# Quad_FC_power_V10_6.net
KiCad netlist of a schematic drawn in Altium Designer
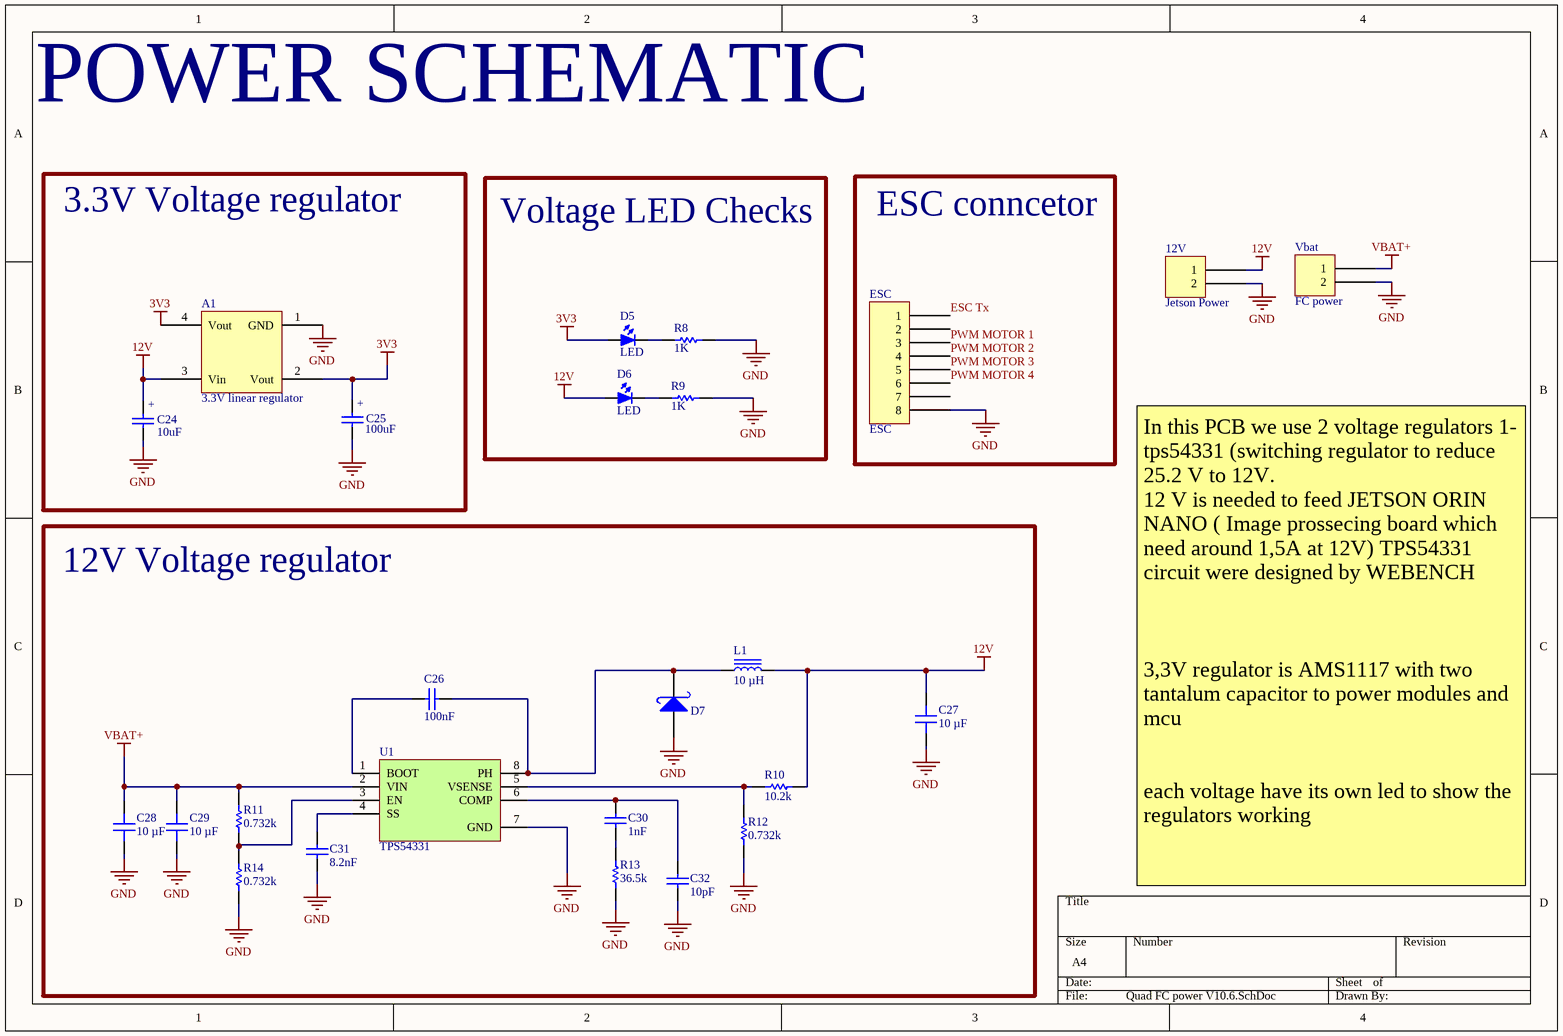
[diagram p0: Quad FC power V10.6.SchDoc]

(export (version "E")
  (design (tool "Eeschema 10.0.6"))
  (components
    (comp (ref "12V")
      (value "Jetson Power")
      (footprint "JST XH B2B-XH-A")
      (description "CONN HEADER VERT 2POS 2.5MM")
      (fields
        (field (name "PART NUMBER") "B2B-XH-A(LF)(SN)")
        (field (name "MANUFACTURER") "JST Sales America Inc.")
      )
      (libsource (lib "Celestial Altium Library - altium_library (1)") (part "2 Pin"))
    )
    (comp (ref "A1")
      (value "3.3V linear regulator")
      (footprint "SOT230P700X180-4N")
      (libsource (lib "Integrated_Library1") (part "ams1117"))
    )
    (comp (ref "C24")
      (value "10uF")
      (footprint "MY_CAP_SMD-B")
      (description "3.5X2.8MM")
      (libsource (lib "AMINLIB") (part "CAP_TANTAL_B"))
    )
    (comp (ref "C25")
      (value "100uF")
      (footprint "MY_CAP_SMD-B")
      (description "3.5X2.8MM")
      (libsource (lib "AMINLIB") (part "CAP_TANTAL_B"))
    )
    (comp (ref "C26")
      (value "100nF")
      (footprint "CAP0603")
      (description "F407VET6 Power CAP")
      (fields (field (name "DESIGNER") "Abbas Basereh"))
      (libsource (lib "2017AbbasBasereh9365731239 -ver1") (part "CAP SMD PACKAGE"))
    )
    (comp (ref "C27")
      (value "10 µF")
      (footprint "CAP 0805_2012")
      (description "CAP CER 10UF 50V X5R 0805")
      (fields
        (field (name "PART NUMBER") "GRM21BR61H106KE43K")
        (field (name "MANUFACTURER") "Murata Electronics")
      )
      (libsource (lib "Celestial Altium Library - altium_library (1)") (part "Capacitor"))
    )
    (comp (ref "C28")
      (value "10 µF")
      (footprint "CAP 0805_2012")
      (description "CAP CER 10UF 50V X5R 0805")
      (fields
        (field (name "PART NUMBER") "GRM21BR61H106KE43K")
        (field (name "MANUFACTURER") "Murata Electronics")
      )
      (libsource (lib "Celestial Altium Library - altium_library (1)") (part "Capacitor"))
    )
    (comp (ref "C29")
      (value "10 µF")
      (footprint "CAP 0805_2012")
      (description "CAP CER 10UF 50V X5R 0805")
      (fields
        (field (name "PART NUMBER") "GRM21BR61H106KE43K")
        (field (name "MANUFACTURER") "Murata Electronics")
      )
      (libsource (lib "Celestial Altium Library - altium_library (1)") (part "Capacitor"))
    )
    (comp (ref "C30")
      (value "1nF")
      (footprint "CAP0603")
      (description "F407VET6 Power CAP")
      (fields (field (name "DESIGNER") "Abbas Basereh"))
      (libsource (lib "2017AbbasBasereh9365731239 -ver1") (part "CAP SMD PACKAGE"))
    )
    (comp (ref "C31")
      (value "8.2nF")
      (footprint "CAP0603")
      (description "F407VET6 Power CAP")
      (fields (field (name "DESIGNER") "Abbas Basereh"))
      (libsource (lib "2017AbbasBasereh9365731239 -ver1") (part "CAP SMD PACKAGE"))
    )
    (comp (ref "C32")
      (value "10pF")
      (footprint "CAP0603")
      (description "F407VET6 Power CAP")
      (fields (field (name "DESIGNER") "Abbas Basereh"))
      (libsource (lib "2017AbbasBasereh9365731239 -ver1") (part "CAP SMD PACKAGE"))
    )
    (comp (ref "D5")
      (value "LED")
      (footprint "0603 - LED")
      (description "Led")
      (fields (field (name "PUBLISHER") "Altium Limited"))
      (libsource (lib "Sajad_Altium_Library") (part "LED"))
    )
    (comp (ref "D6")
      (value "LED")
      (footprint "0603 - LED")
      (description "Led")
      (fields (field (name "PUBLISHER") "Altium Limited"))
      (libsource (lib "Sajad_Altium_Library") (part "LED"))
    )
    (comp (ref "D7")
      (value "1n5822")
      (footprint "SS34:DIOM4226X244N")
      (description "Schottky Rectifiers")
      (fields
        (field (name "MANUFACTURER") "ON Semiconductor/Fairchild")
        (field (name "DESIGNER") "Abbas Basereh")
      )
      (libsource (lib "2017AbbasBasereh9365731239 -ver1") (part "1n5822 SMD"))
    )
    (comp (ref "ESC")
      (value "ESC")
      (footprint "JST BM08B-SRSS-TB")
      (description "CONN HEADER SMD 8POS 1MM")
      (fields (field (name "PART NUMBER") "BM08B-SRSS-TBT(LF)(SN)"))
      (libsource (lib "Celestial Altium Library - altium_library (1)") (part "8 Pin"))
    )
    (comp (ref "L1")
      (value "10 µH")
      (footprint "TAIYO YUDEN NRS8030")
      (description "FIXED IND 10UH 3A 42.9 MOHM SMD")
      (fields (field (name "PART NUMBER") "NRS8030T100MJGJV") (field (name "MANUFACTURER") "Taiyo Yuden"))
      (libsource (lib "Celestial Altium Library - altium_library (1)") (part "Inductor"))
    )
    (comp (ref "R8")
      (value "1K")
      (footprint "RES0603")
      (description "TOTAL SMD RESISTOR PACK")
      (fields (field (name "DESIGNER") "Abbas Basereh"))
      (libsource (lib "2017AbbasBasereh9365731239 -ver1") (part "RES SMD PACKAGE"))
    )
    (comp (ref "R9")
      (value "1K")
      (footprint "RES0603")
      (description "TOTAL SMD RESISTOR PACK")
      (fields (field (name "DESIGNER") "Abbas Basereh"))
      (libsource (lib "2017AbbasBasereh9365731239 -ver1") (part "RES SMD PACKAGE"))
    )
    (comp (ref "R10")
      (value "10.2k")
      (footprint "RES0603")
      (description "TOTAL SMD RESISTOR PACK")
      (fields (field (name "DESIGNER") "Abbas Basereh"))
      (libsource (lib "2017AbbasBasereh9365731239 -ver1") (part "RES SMD PACKAGE"))
    )
    (comp (ref "R11")
      (value "0.732k")
      (footprint "RES0603")
      (description "TOTAL SMD RESISTOR PACK")
      (fields (field (name "DESIGNER") "Abbas Basereh"))
      (libsource (lib "2017AbbasBasereh9365731239 -ver1") (part "RES SMD PACKAGE"))
    )
    (comp (ref "R12")
      (value "0.732k")
      (footprint "RES0603")
      (description "TOTAL SMD RESISTOR PACK")
      (fields (field (name "DESIGNER") "Abbas Basereh"))
      (libsource (lib "2017AbbasBasereh9365731239 -ver1") (part "RES SMD PACKAGE"))
    )
    (comp (ref "R13")
      (value "36.5k")
      (footprint "RES0603")
      (description "TOTAL SMD RESISTOR PACK")
      (fields (field (name "Comment") "36.5K") (field (name "DESIGNER") "Abbas Basereh"))
      (libsource (lib "2017AbbasBasereh9365731239 -ver1") (part "RES SMD PACKAGE"))
    )
    (comp (ref "R14")
      (value "0.732k")
      (footprint "RES0603")
      (description "TOTAL SMD RESISTOR PACK")
      (fields (field (name "DESIGNER") "Abbas Basereh"))
      (libsource (lib "2017AbbasBasereh9365731239 -ver1") (part "RES SMD PACKAGE"))
    )
    (comp (ref "U1")
      (value "TPS54331")
      (footprint "SO8")
      (description "DC/DC Switching Regulators 2A,28V,1MHz Step Down SWIFT DC/D;Output Voltage:0.8 V to 25 V")
      (libsource (lib "Sajad_Altium_Library") (part "TPS54331"))
    )
    (comp (ref "Vbat")
      (value "FC power")
      (footprint "JST XH B2B-XH-A")
      (description "CONN HEADER VERT 2POS 2.5MM")
      (fields
        (field (name "PART NUMBER") "B2B-XH-A(LF)(SN)")
        (field (name "MANUFACTURER") "JST Sales America Inc.")
      )
      (libsource (lib "Celestial Altium Library - altium_library (1)") (part "2 Pin"))
    )
  )
  (nets
    (net (code "1") (name "/ESC Tx") (class "Default")
      (node (ref "ESC") (pin "1") (pinfunction "1_1") (pintype "passive"))
    )
    (net (code "2") (name "/PWM MOTOR 1") (class "Default")
      (node (ref "ESC") (pin "3") (pinfunction "3_3") (pintype "passive"))
    )
    (net (code "3") (name "/PWM MOTOR 2") (class "Default")
      (node (ref "ESC") (pin "4") (pinfunction "4_4") (pintype "passive"))
    )
    (net (code "4") (name "/PWM MOTOR 3") (class "Default")
      (node (ref "ESC") (pin "5") (pinfunction "5_5") (pintype "passive"))
    )
    (net (code "5") (name "/PWM MOTOR 4") (class "Default")
      (node (ref "ESC") (pin "6") (pinfunction "6_6") (pintype "passive"))
    )
    (net (code "6") (name "3V3") (class "Default")
      (node (ref "A1") (pin "2") (pinfunction "Vout_2") (pintype "passive"))
      (node (ref "A1") (pin "4") (pinfunction "Vout_4") (pintype "passive"))
      (node (ref "C25") (pin "+") (pinfunction "+_+") (pintype "passive"))
      (node (ref "D5") (pin "1") (pinfunction "A_1") (pintype "passive"))
    )
    (net (code "7") (name "12V") (class "Default")
      (node (ref "12V") (pin "1") (pinfunction "1_1") (pintype "passive"))
      (node (ref "A1") (pin "3") (pinfunction "Vin_3") (pintype "passive"))
      (node (ref "C24") (pin "+") (pinfunction "+_+") (pintype "passive"))
      (node (ref "C27") (pin "2") (pinfunction "2_2") (pintype "passive"))
      (node (ref "D6") (pin "1") (pinfunction "A_1") (pintype "passive"))
      (node (ref "L1") (pin "2") (pinfunction "2_2") (pintype "passive"))
      (node (ref "R10") (pin "2") (pinfunction "2_2") (pintype "passive"))
    )
    (net (code "8") (name "GND") (class "Default")
      (node (ref "12V") (pin "2") (pinfunction "2_2") (pintype "passive"))
      (node (ref "A1") (pin "1") (pinfunction "GND_1") (pintype "passive"))
      (node (ref "C24") (pin "-") (pinfunction "-_-") (pintype "passive"))
      (node (ref "C25") (pin "-") (pinfunction "-_-") (pintype "passive"))
      (node (ref "C27") (pin "1") (pinfunction "1_1") (pintype "passive"))
      (node (ref "C28") (pin "1") (pinfunction "1_1") (pintype "passive"))
      (node (ref "C29") (pin "1") (pinfunction "1_1") (pintype "passive"))
      (node (ref "C31") (pin "2") (pinfunction "2_2") (pintype "passive"))
      (node (ref "C32") (pin "2") (pinfunction "2_2") (pintype "passive"))
      (node (ref "D7") (pin "1") (pinfunction "A_1") (pintype "passive"))
      (node (ref "ESC") (pin "8") (pinfunction "8_8") (pintype "passive"))
      (node (ref "R12") (pin "1") (pinfunction "1_1") (pintype "passive"))
      (node (ref "R13") (pin "1") (pinfunction "1_1") (pintype "passive"))
      (node (ref "R14") (pin "1") (pinfunction "1_1") (pintype "passive"))
      (node (ref "R8") (pin "2") (pinfunction "2_2") (pintype "passive"))
      (node (ref "R9") (pin "2") (pinfunction "2_2") (pintype "passive"))
      (node (ref "U1") (pin "7") (pinfunction "GND_7") (pintype "passive"))
      (node (ref "Vbat") (pin "2") (pinfunction "2_2") (pintype "passive"))
    )
    (net (code "9") (name "Net-(C30-Pad2)") (class "Default")
      (node (ref "C30") (pin "2") (pinfunction "2_2") (pintype "passive"))
      (node (ref "R13") (pin "2") (pinfunction "2_2") (pintype "passive"))
    )
    (net (code "10") (name "Net-(D5-K)") (class "Default")
      (node (ref "D5") (pin "2") (pinfunction "K_2") (pintype "passive"))
      (node (ref "R8") (pin "1") (pinfunction "1_1") (pintype "passive"))
    )
    (net (code "11") (name "Net-(D6-K)") (class "Default")
      (node (ref "D6") (pin "2") (pinfunction "K_2") (pintype "passive"))
      (node (ref "R9") (pin "1") (pinfunction "1_1") (pintype "passive"))
    )
    (net (code "12") (name "Net-(D7-K)") (class "Default")
      (node (ref "C26") (pin "1") (pinfunction "1_1") (pintype "passive"))
      (node (ref "D7") (pin "2") (pinfunction "K_2") (pintype "passive"))
      (node (ref "L1") (pin "1") (pinfunction "1_1") (pintype "passive"))
      (node (ref "U1") (pin "8") (pinfunction "PH_8") (pintype "open_collector"))
    )
    (net (code "13") (name "Net-(U1-BOOT)") (class "Default")
      (node (ref "C26") (pin "2") (pinfunction "2_2") (pintype "passive"))
      (node (ref "U1") (pin "1") (pinfunction "BOOT_1") (pintype "passive"))
    )
    (net (code "14") (name "Net-(U1-COMP)") (class "Default")
      (node (ref "C30") (pin "1") (pinfunction "1_1") (pintype "passive"))
      (node (ref "C32") (pin "1") (pinfunction "1_1") (pintype "passive"))
      (node (ref "U1") (pin "6") (pinfunction "COMP_6") (pintype "power_in"))
    )
    (net (code "15") (name "Net-(U1-EN)") (class "Default")
      (node (ref "R11") (pin "1") (pinfunction "1_1") (pintype "passive"))
      (node (ref "R14") (pin "2") (pinfunction "2_2") (pintype "passive"))
      (node (ref "U1") (pin "3") (pinfunction "EN_3") (pintype "passive"))
    )
    (net (code "16") (name "Net-(U1-SS)") (class "Default")
      (node (ref "C31") (pin "1") (pinfunction "1_1") (pintype "passive"))
      (node (ref "U1") (pin "4") (pinfunction "SS_4") (pintype "power_in"))
    )
    (net (code "17") (name "Net-(U1-VSENSE)") (class "Default")
      (node (ref "R10") (pin "1") (pinfunction "1_1") (pintype "passive"))
      (node (ref "R12") (pin "2") (pinfunction "2_2") (pintype "passive"))
      (node (ref "U1") (pin "5") (pinfunction "VSENSE_5") (pintype "passive"))
    )
    (net (code "18") (name "VBAT+") (class "Default")
      (node (ref "C28") (pin "2") (pinfunction "2_2") (pintype "passive"))
      (node (ref "C29") (pin "2") (pinfunction "2_2") (pintype "passive"))
      (node (ref "R11") (pin "2") (pinfunction "2_2") (pintype "passive"))
      (node (ref "U1") (pin "2") (pinfunction "VIN_2") (pintype "passive"))
      (node (ref "Vbat") (pin "1") (pinfunction "1_1") (pintype "passive"))
    )
    (net (code "19") (name "unconnected-(ESC-Pad2)") (class "Default")
      (node (ref "ESC") (pin "2") (pinfunction "2_2") (pintype "passive"))
    )
    (net (code "20") (name "unconnected-(ESC-Pad7)") (class "Default")
      (node (ref "ESC") (pin "7") (pinfunction "7_7") (pintype "passive"))
    )
  )
)
